# cpu.net
KiCad netlist of a schematic drawn in Altium Designer
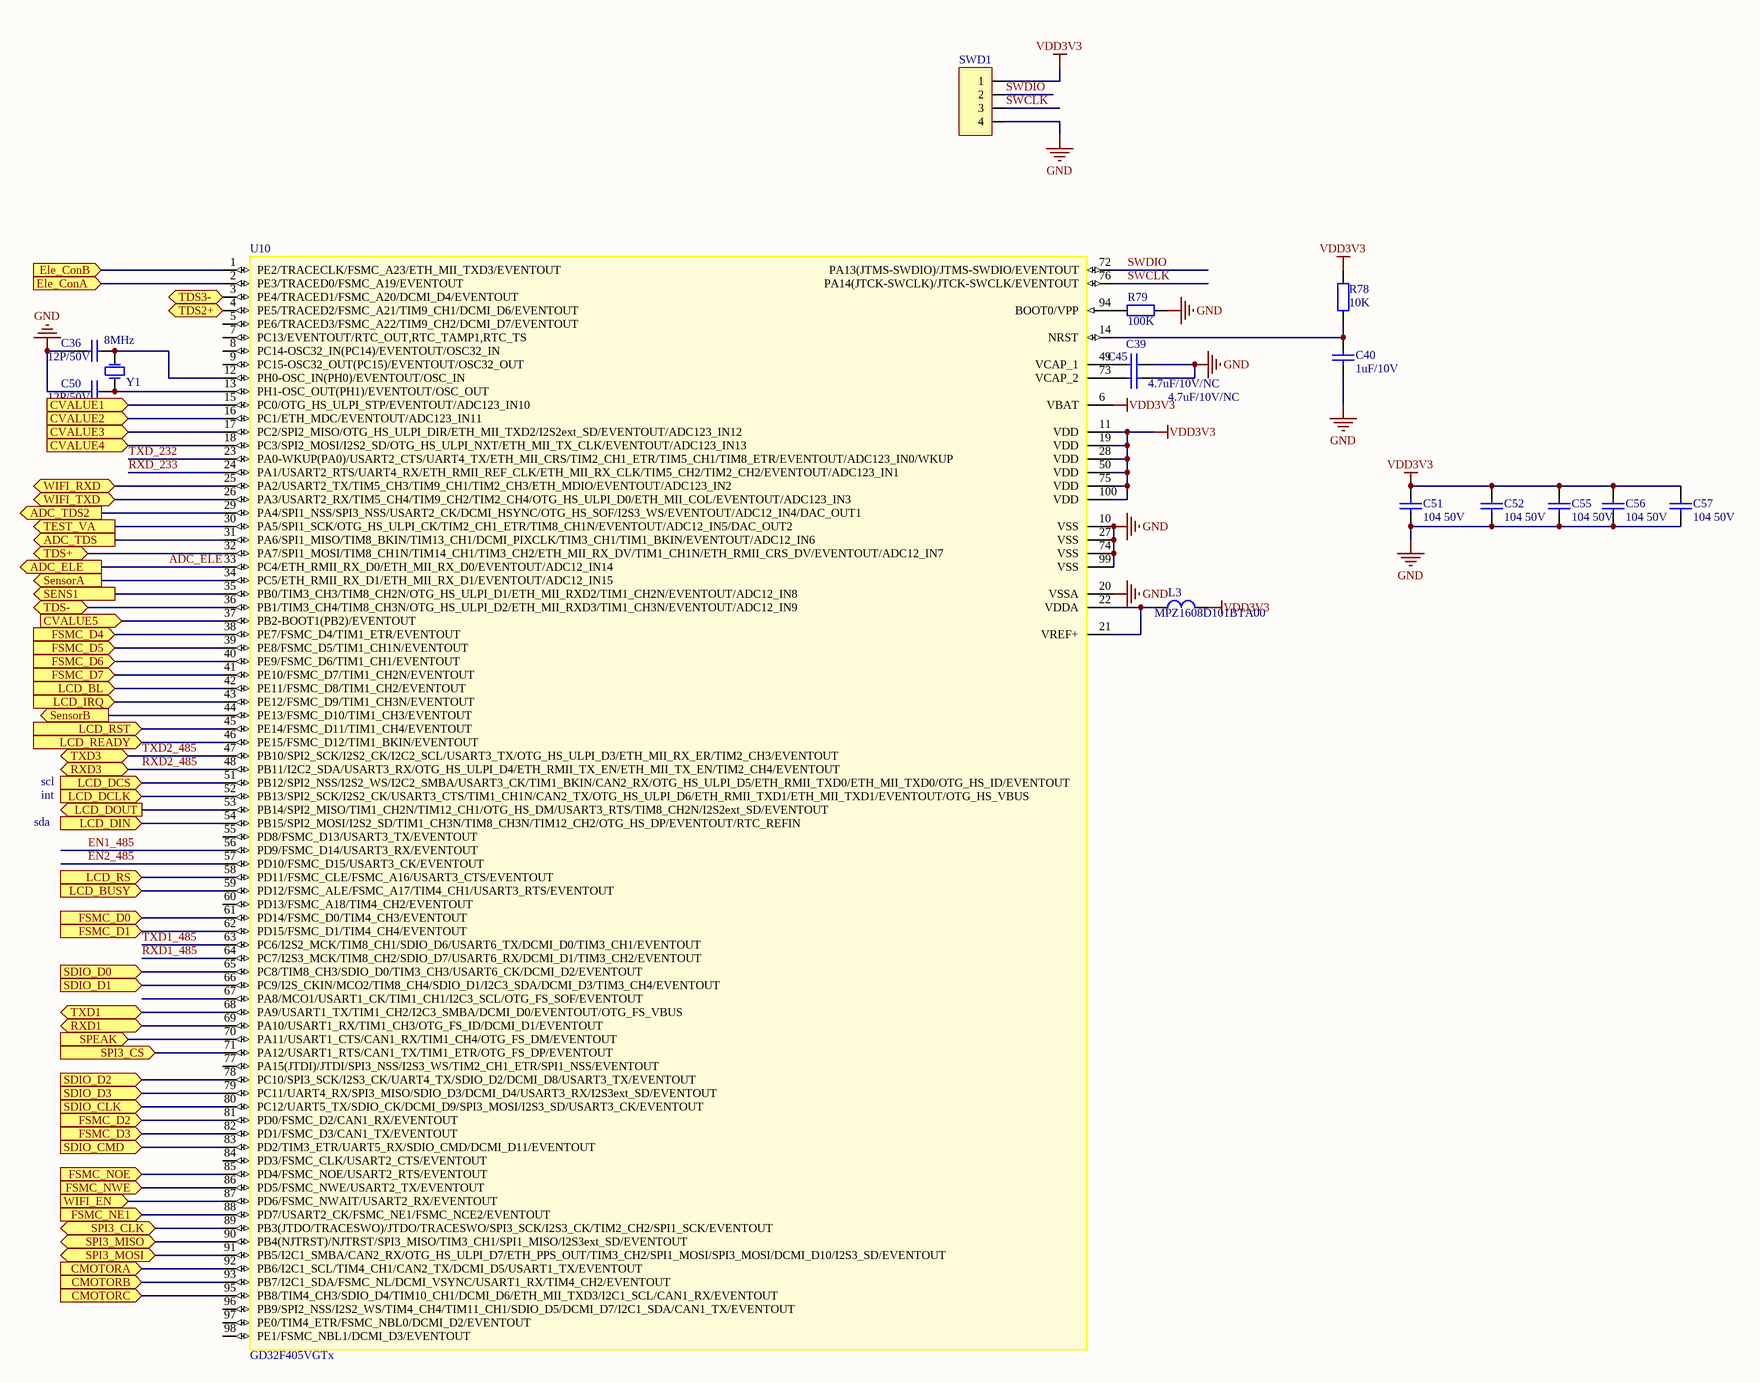
[diagram p0: cpu.SchDoc]

(export (version "E")
  (design (tool "Eeschema 10.0.6"))
  (components
    (comp (ref "C36")
      (value "12P/50V")
      (footprint "SMD-0603C")
      (description "贴片电容 5%")
      (libsource (lib "XiaoyI") (part "CAP4"))
    )
    (comp (ref "C39")
      (value "4.7uF/10V/NC")
      (footprint "SMD-0603C")
      (description "贴片电容 20%")
      (libsource (lib "XiaoyI") (part "CAP4"))
    )
    (comp (ref "C40")
      (value "1uF/10V")
      (footprint "SMD-0603C")
      (description "贴片电容 20%")
      (libsource (lib "XiaoyI") (part "CAP4"))
    )
    (comp (ref "C45")
      (value "4.7uF/10V/NC")
      (footprint "SMD-0603C")
      (description "贴片电容 20%")
      (libsource (lib "XiaoyI") (part "CAP4"))
    )
    (comp (ref "C50")
      (value "12P/50V")
      (footprint "SMD-0603C")
      (description "贴片电容 5%")
      (libsource (lib "XiaoyI") (part "CAP4"))
    )
    (comp (ref "C51")
      (value "104 50V")
      (footprint "SMD-0603C")
      (description "贴片电容 20%")
      (libsource (lib "XiaoyI") (part "CAP4"))
    )
    (comp (ref "C52")
      (value "104 50V")
      (footprint "SMD-0603C")
      (description "贴片电容 20%")
      (libsource (lib "XiaoyI") (part "CAP4"))
    )
    (comp (ref "C55")
      (value "104 50V")
      (footprint "SMD-0603C")
      (description "贴片电容 20%")
      (libsource (lib "XiaoyI") (part "CAP4"))
    )
    (comp (ref "C56")
      (value "104 50V")
      (footprint "SMD-0603C")
      (description "贴片电容 20%")
      (libsource (lib "XiaoyI") (part "CAP4"))
    )
    (comp (ref "C57")
      (value "104 50V")
      (footprint "SMD-0603C")
      (description "贴片电容 20%")
      (libsource (lib "XiaoyI") (part "CAP4"))
    )
    (comp (ref "L3")
      (value "MPZ1608D101BTA00")
      (footprint "SMD-0603")
      (description "磁珠电感 100R 100MHz")
      (libsource (lib "XiaoyI") (part "CIZHU1"))
    )
    (comp (ref "R78")
      (value "10K")
      (footprint "SMD-0603")
      (description "贴片电阻 5%")
      (libsource (lib "XiaoyI") (part "RES2"))
    )
    (comp (ref "R79")
      (value "100K")
      (footprint "SMD-0603")
      (description "贴片电阻 5%")
      (libsource (lib "") (part "RES2_1"))
    )
    (comp (ref "SWD1")
      (value "SIP-4 (NC)")
      (footprint "SIP-4")
      (description "ISP 下载")
      (libsource (lib "XiaoyI") (part "SIP-4"))
    )
    (comp (ref "U10")
      (value "GD32F405VGTx")
      (footprint "STM-LQFP100_N")
      (fields (field (name "MANUFACTURER") "STMicroelectronics") (field (name "PARTNUMBER") "STM32F405VGT6"))
      (libsource (lib "STM32F4") (part "STM32F405VGTx"))
    )
    (comp (ref "Y1")
      (value "8MHz")
      (footprint "XTAL-3225-2")
      (description "3225 贴片晶振")
      (libsource (lib "XiaoyI") (part "XTAL"))
    )
  )
  (nets
    (net (code "1") (name "/ADC_ELE") (class "Default")
      (node (ref "U10") (pin "33") (pinfunction "PC4/ETH_RMII_RX_D0/ETH_MII_RX_D0/EVENTOUT/ADC12_IN14_33") (pintype "bidirectional"))
    )
    (net (code "2") (name "/ADC_TDS") (class "Default")
      (node (ref "U10") (pin "31") (pinfunction "PA6/SPI1_MISO/TIM8_BKIN/TIM13_CH1/DCMI_PIXCLK/TIM3_CH1/TIM1_BKIN/EVENTOUT/ADC12_IN6_31") (pintype "bidirectional"))
    )
    (net (code "3") (name "/ADC_TDS2") (class "Default")
      (node (ref "U10") (pin "29") (pinfunction "PA4/SPI1_NSS/SPI3_NSS/USART2_CK/DCMI_HSYNC/OTG_HS_SOF/I2S3_WS/EVENTOUT/ADC12_IN4/DAC_OUT1_29") (pintype "bidirectional"))
    )
    (net (code "4") (name "/CMOTORA") (class "Default")
      (node (ref "U10") (pin "92") (pinfunction "PB6/I2C1_SCL/TIM4_CH1/CAN2_TX/DCMI_D5/USART1_TX/EVENTOUT_92") (pintype "bidirectional"))
    )
    (net (code "5") (name "/CMOTORB") (class "Default")
      (node (ref "U10") (pin "93") (pinfunction "PB7/I2C1_SDA/FSMC_NL/DCMI_VSYNC/USART1_RX/TIM4_CH2/EVENTOUT_93") (pintype "bidirectional"))
    )
    (net (code "6") (name "/CMOTORC") (class "Default")
      (node (ref "U10") (pin "95") (pinfunction "PB8/TIM4_CH3/SDIO_D4/TIM10_CH1/DCMI_D6/ETH_MII_TXD3/I2C1_SCL/CAN1_RX/EVENTOUT_95") (pintype "bidirectional"))
    )
    (net (code "7") (name "/CVALUE1") (class "Default")
      (node (ref "U10") (pin "15") (pinfunction "PC0/OTG_HS_ULPI_STP/EVENTOUT/ADC123_IN10_15") (pintype "bidirectional"))
    )
    (net (code "8") (name "/CVALUE2") (class "Default")
      (node (ref "U10") (pin "16") (pinfunction "PC1/ETH_MDC/EVENTOUT/ADC123_IN11_16") (pintype "bidirectional"))
    )
    (net (code "9") (name "/CVALUE3") (class "Default")
      (node (ref "U10") (pin "17") (pinfunction "PC2/SPI2_MISO/OTG_HS_ULPI_DIR/ETH_MII_TXD2/I2S2ext_SD/EVENTOUT/ADC123_IN12_17") (pintype "bidirectional"))
    )
    (net (code "10") (name "/CVALUE4") (class "Default")
      (node (ref "U10") (pin "18") (pinfunction "PC3/SPI2_MOSI/I2S2_SD/OTG_HS_ULPI_NXT/ETH_MII_TX_CLK/EVENTOUT/ADC123_IN13_18") (pintype "bidirectional"))
    )
    (net (code "11") (name "/CVALUE5") (class "Default")
      (node (ref "U10") (pin "37") (pinfunction "PB2-BOOT1(PB2)/EVENTOUT_37") (pintype "bidirectional"))
    )
    (net (code "12") (name "/EN1_485") (class "Default")
      (node (ref "U10") (pin "56") (pinfunction "PD9/FSMC_D14/USART3_RX/EVENTOUT_56") (pintype "bidirectional"))
    )
    (net (code "13") (name "/EN2_485") (class "Default")
      (node (ref "U10") (pin "57") (pinfunction "PD10/FSMC_D15/USART3_CK/EVENTOUT_57") (pintype "bidirectional"))
    )
    (net (code "14") (name "/Ele_ConA") (class "Default")
      (node (ref "U10") (pin "2") (pinfunction "PE3/TRACED0/FSMC_A19/EVENTOUT_2") (pintype "bidirectional"))
    )
    (net (code "15") (name "/Ele_ConB") (class "Default")
      (node (ref "U10") (pin "1") (pinfunction "PE2/TRACECLK/FSMC_A23/ETH_MII_TXD3/EVENTOUT_1") (pintype "bidirectional"))
    )
    (net (code "16") (name "/FSMC_D0") (class "Default")
      (node (ref "U10") (pin "61") (pinfunction "PD14/FSMC_D0/TIM4_CH3/EVENTOUT_61") (pintype "bidirectional"))
    )
    (net (code "17") (name "/FSMC_D1") (class "Default")
      (node (ref "U10") (pin "62") (pinfunction "PD15/FSMC_D1/TIM4_CH4/EVENTOUT_62") (pintype "bidirectional"))
    )
    (net (code "18") (name "/FSMC_D2") (class "Default")
      (node (ref "U10") (pin "81") (pinfunction "PD0/FSMC_D2/CAN1_RX/EVENTOUT_81") (pintype "bidirectional"))
    )
    (net (code "19") (name "/FSMC_D3") (class "Default")
      (node (ref "U10") (pin "82") (pinfunction "PD1/FSMC_D3/CAN1_TX/EVENTOUT_82") (pintype "bidirectional"))
    )
    (net (code "20") (name "/FSMC_D4") (class "Default")
      (node (ref "U10") (pin "38") (pinfunction "PE7/FSMC_D4/TIM1_ETR/EVENTOUT_38") (pintype "bidirectional"))
    )
    (net (code "21") (name "/FSMC_D5") (class "Default")
      (node (ref "U10") (pin "39") (pinfunction "PE8/FSMC_D5/TIM1_CH1N/EVENTOUT_39") (pintype "bidirectional"))
    )
    (net (code "22") (name "/FSMC_D6") (class "Default")
      (node (ref "U10") (pin "40") (pinfunction "PE9/FSMC_D6/TIM1_CH1/EVENTOUT_40") (pintype "bidirectional"))
    )
    (net (code "23") (name "/FSMC_D7") (class "Default")
      (node (ref "U10") (pin "41") (pinfunction "PE10/FSMC_D7/TIM1_CH2N/EVENTOUT_41") (pintype "bidirectional"))
    )
    (net (code "24") (name "/FSMC_NE1") (class "Default")
      (node (ref "U10") (pin "88") (pinfunction "PD7/USART2_CK/FSMC_NE1/FSMC_NCE2/EVENTOUT_88") (pintype "bidirectional"))
    )
    (net (code "25") (name "/FSMC_NOE") (class "Default")
      (node (ref "U10") (pin "85") (pinfunction "PD4/FSMC_NOE/USART2_RTS/EVENTOUT_85") (pintype "bidirectional"))
    )
    (net (code "26") (name "/FSMC_NWE") (class "Default")
      (node (ref "U10") (pin "86") (pinfunction "PD5/FSMC_NWE/USART2_TX/EVENTOUT_86") (pintype "bidirectional"))
    )
    (net (code "27") (name "/LCD_BL") (class "Default")
      (node (ref "U10") (pin "42") (pinfunction "PE11/FSMC_D8/TIM1_CH2/EVENTOUT_42") (pintype "bidirectional"))
    )
    (net (code "28") (name "/LCD_BUSY") (class "Default")
      (node (ref "U10") (pin "59") (pinfunction "PD12/FSMC_ALE/FSMC_A17/TIM4_CH1/USART3_RTS/EVENTOUT_59") (pintype "bidirectional"))
    )
    (net (code "29") (name "/LCD_DCLK") (class "Default")
      (node (ref "U10") (pin "52") (pinfunction "PB13/SPI2_SCK/I2S2_CK/USART3_CTS/TIM1_CH1N/CAN2_TX/OTG_HS_ULPI_D6/ETH_RMII_TXD1/ETH_MII_TXD1/EVENTOUT/OTG_HS_VBUS_52") (pintype "bidirectional"))
    )
    (net (code "30") (name "/LCD_DCS") (class "Default")
      (node (ref "U10") (pin "51") (pinfunction "PB12/SPI2_NSS/I2S2_WS/I2C2_SMBA/USART3_CK/TIM1_BKIN/CAN2_RX/OTG_HS_ULPI_D5/ETH_RMII_TXD0/ETH_MII_TXD0/OTG_HS_ID/EVENTOUT_51") (pintype "bidirectional"))
    )
    (net (code "31") (name "/LCD_DIN") (class "Default")
      (node (ref "U10") (pin "54") (pinfunction "PB15/SPI2_MOSI/I2S2_SD/TIM1_CH3N/TIM8_CH3N/TIM12_CH2/OTG_HS_DP/EVENTOUT/RTC_REFIN_54") (pintype "bidirectional"))
    )
    (net (code "32") (name "/LCD_DOUT") (class "Default")
      (node (ref "U10") (pin "53") (pinfunction "PB14/SPI2_MISO/TIM1_CH2N/TIM12_CH1/OTG_HS_DM/USART3_RTS/TIM8_CH2N/I2S2ext_SD/EVENTOUT_53") (pintype "bidirectional"))
    )
    (net (code "33") (name "/LCD_IRQ") (class "Default")
      (node (ref "U10") (pin "43") (pinfunction "PE12/FSMC_D9/TIM1_CH3N/EVENTOUT_43") (pintype "bidirectional"))
    )
    (net (code "34") (name "/LCD_READY") (class "Default")
      (node (ref "U10") (pin "46") (pinfunction "PE15/FSMC_D12/TIM1_BKIN/EVENTOUT_46") (pintype "bidirectional"))
    )
    (net (code "35") (name "/LCD_RS") (class "Default")
      (node (ref "U10") (pin "58") (pinfunction "PD11/FSMC_CLE/FSMC_A16/USART3_CTS/EVENTOUT_58") (pintype "bidirectional"))
    )
    (net (code "36") (name "/LCD_RST") (class "Default")
      (node (ref "U10") (pin "45") (pinfunction "PE14/FSMC_D11/TIM1_CH4/EVENTOUT_45") (pintype "bidirectional"))
    )
    (net (code "37") (name "/RXD1") (class "Default")
      (node (ref "U10") (pin "69") (pinfunction "PA10/USART1_RX/TIM1_CH3/OTG_FS_ID/DCMI_D1/EVENTOUT_69") (pintype "bidirectional"))
    )
    (net (code "38") (name "/RXD1_485") (class "Default")
      (node (ref "U10") (pin "64") (pinfunction "PC7/I2S3_MCK/TIM8_CH2/SDIO_D7/USART6_RX/DCMI_D1/TIM3_CH2/EVENTOUT_64") (pintype "bidirectional"))
    )
    (net (code "39") (name "/RXD2_485") (class "Default")
      (node (ref "U10") (pin "48") (pinfunction "PB11/I2C2_SDA/USART3_RX/OTG_HS_ULPI_D4/ETH_RMII_TX_EN/ETH_MII_TX_EN/TIM2_CH4/EVENTOUT_48") (pintype "bidirectional"))
    )
    (net (code "40") (name "/RXD_233") (class "Default")
      (node (ref "U10") (pin "24") (pinfunction "PA1/USART2_RTS/UART4_RX/ETH_RMII_REF_CLK/ETH_MII_RX_CLK/TIM5_CH2/TIM2_CH2/EVENTOUT/ADC123_IN1_24") (pintype "bidirectional"))
    )
    (net (code "41") (name "/SDIO_CLK") (class "Default")
      (node (ref "U10") (pin "80") (pinfunction "PC12/UART5_TX/SDIO_CK/DCMI_D9/SPI3_MOSI/I2S3_SD/USART3_CK/EVENTOUT_80") (pintype "bidirectional"))
    )
    (net (code "42") (name "/SDIO_CMD") (class "Default")
      (node (ref "U10") (pin "83") (pinfunction "PD2/TIM3_ETR/UART5_RX/SDIO_CMD/DCMI_D11/EVENTOUT_83") (pintype "bidirectional"))
    )
    (net (code "43") (name "/SDIO_D0") (class "Default")
      (node (ref "U10") (pin "65") (pinfunction "PC8/TIM8_CH3/SDIO_D0/TIM3_CH3/USART6_CK/DCMI_D2/EVENTOUT_65") (pintype "bidirectional"))
    )
    (net (code "44") (name "/SDIO_D1") (class "Default")
      (node (ref "U10") (pin "66") (pinfunction "PC9/I2S_CKIN/MCO2/TIM8_CH4/SDIO_D1/I2C3_SDA/DCMI_D3/TIM3_CH4/EVENTOUT_66") (pintype "bidirectional"))
    )
    (net (code "45") (name "/SDIO_D2") (class "Default")
      (node (ref "U10") (pin "78") (pinfunction "PC10/SPI3_SCK/I2S3_CK/UART4_TX/SDIO_D2/DCMI_D8/USART3_TX/EVENTOUT_78") (pintype "bidirectional"))
    )
    (net (code "46") (name "/SDIO_D3") (class "Default")
      (node (ref "U10") (pin "79") (pinfunction "PC11/UART4_RX/SPI3_MISO/SDIO_D3/DCMI_D4/USART3_RX/I2S3ext_SD/EVENTOUT_79") (pintype "bidirectional"))
    )
    (net (code "47") (name "/SENS1") (class "Default")
      (node (ref "U10") (pin "35") (pinfunction "PB0/TIM3_CH3/TIM8_CH2N/OTG_HS_ULPI_D1/ETH_MII_RXD2/TIM1_CH2N/EVENTOUT/ADC12_IN8_35") (pintype "bidirectional"))
    )
    (net (code "48") (name "/SPEAK") (class "Default")
      (node (ref "U10") (pin "70") (pinfunction "PA11/USART1_CTS/CAN1_RX/TIM1_CH4/OTG_FS_DM/EVENTOUT_70") (pintype "bidirectional"))
    )
    (net (code "49") (name "/SPI3_CLK") (class "Default")
      (node (ref "U10") (pin "89") (pinfunction "PB3(JTDO/TRACESWO)/JTDO/TRACESWO/SPI3_SCK/I2S3_CK/TIM2_CH2/SPI1_SCK/EVENTOUT_89") (pintype "bidirectional"))
    )
    (net (code "50") (name "/SPI3_CS") (class "Default")
      (node (ref "U10") (pin "71") (pinfunction "PA12/USART1_RTS/CAN1_TX/TIM1_ETR/OTG_FS_DP/EVENTOUT_71") (pintype "bidirectional"))
    )
    (net (code "51") (name "/SPI3_MISO") (class "Default")
      (node (ref "U10") (pin "90") (pinfunction "PB4(NJTRST)/NJTRST/SPI3_MISO/TIM3_CH1/SPI1_MISO/I2S3ext_SD/EVENTOUT_90") (pintype "bidirectional"))
    )
    (net (code "52") (name "/SPI3_MOSI") (class "Default")
      (node (ref "U10") (pin "91") (pinfunction "PB5/I2C1_SMBA/CAN2_RX/OTG_HS_ULPI_D7/ETH_PPS_OUT/TIM3_CH2/SPI1_MOSI/SPI3_MOSI/DCMI_D10/I2S3_SD/EVENTOUT_91") (pintype "bidirectional"))
    )
    (net (code "53") (name "/SWCLK") (class "Default")
      (node (ref "SWD1") (pin "3") (pinfunction "3_3") (pintype "passive"))
      (node (ref "U10") (pin "76") (pinfunction "PA14(JTCK-SWCLK)/JTCK-SWCLK/EVENTOUT_76") (pintype "bidirectional"))
    )
    (net (code "54") (name "/SWDIO") (class "Default")
      (node (ref "SWD1") (pin "2") (pinfunction "2_2") (pintype "passive"))
      (node (ref "U10") (pin "72") (pinfunction "PA13(JTMS-SWDIO)/JTMS-SWDIO/EVENTOUT_72") (pintype "bidirectional"))
    )
    (net (code "55") (name "/SensorA") (class "Default")
      (node (ref "U10") (pin "34") (pinfunction "PC5/ETH_RMII_RX_D1/ETH_MII_RX_D1/EVENTOUT/ADC12_IN15_34") (pintype "bidirectional"))
    )
    (net (code "56") (name "/SensorB") (class "Default")
      (node (ref "U10") (pin "44") (pinfunction "PE13/FSMC_D10/TIM1_CH3/EVENTOUT_44") (pintype "bidirectional"))
    )
    (net (code "57") (name "/TDS+") (class "Default")
      (node (ref "U10") (pin "32") (pinfunction "PA7/SPI1_MOSI/TIM8_CH1N/TIM14_CH1/TIM3_CH2/ETH_MII_RX_DV/TIM1_CH1N/ETH_RMII_CRS_DV/EVENTOUT/ADC12_IN7_32") (pintype "bidirectional"))
    )
    (net (code "58") (name "/TDS-") (class "Default")
      (node (ref "U10") (pin "36") (pinfunction "PB1/TIM3_CH4/TIM8_CH3N/OTG_HS_ULPI_D2/ETH_MII_RXD3/TIM1_CH3N/EVENTOUT/ADC12_IN9_36") (pintype "bidirectional"))
    )
    (net (code "59") (name "/TDS2+") (class "Default")
      (node (ref "U10") (pin "4") (pinfunction "PE5/TRACED2/FSMC_A21/TIM9_CH1/DCMI_D6/EVENTOUT_4") (pintype "bidirectional"))
    )
    (net (code "60") (name "/TDS3-") (class "Default")
      (node (ref "U10") (pin "3") (pinfunction "PE4/TRACED1/FSMC_A20/DCMI_D4/EVENTOUT_3") (pintype "bidirectional"))
    )
    (net (code "61") (name "/TEST_VA") (class "Default")
      (node (ref "U10") (pin "30") (pinfunction "PA5/SPI1_SCK/OTG_HS_ULPI_CK/TIM2_CH1_ETR/TIM8_CH1N/EVENTOUT/ADC12_IN5/DAC_OUT2_30") (pintype "bidirectional"))
    )
    (net (code "62") (name "/TXD1") (class "Default")
      (node (ref "U10") (pin "68") (pinfunction "PA9/USART1_TX/TIM1_CH2/I2C3_SMBA/DCMI_D0/EVENTOUT/OTG_FS_VBUS_68") (pintype "bidirectional"))
    )
    (net (code "63") (name "/TXD1_485") (class "Default")
      (node (ref "U10") (pin "63") (pinfunction "PC6/I2S2_MCK/TIM8_CH1/SDIO_D6/USART6_TX/DCMI_D0/TIM3_CH1/EVENTOUT_63") (pintype "bidirectional"))
    )
    (net (code "64") (name "/TXD2_485") (class "Default")
      (node (ref "U10") (pin "47") (pinfunction "PB10/SPI2_SCK/I2S2_CK/I2C2_SCL/USART3_TX/OTG_HS_ULPI_D3/ETH_MII_RX_ER/TIM2_CH3/EVENTOUT_47") (pintype "bidirectional"))
    )
    (net (code "65") (name "/TXD_232") (class "Default")
      (node (ref "U10") (pin "23") (pinfunction "PA0-WKUP(PA0)/USART2_CTS/UART4_TX/ETH_MII_CRS/TIM2_CH1_ETR/TIM5_CH1/TIM8_ETR/EVENTOUT/ADC123_IN0/WKUP_23") (pintype "bidirectional"))
    )
    (net (code "66") (name "/WIFI_EN") (class "Default")
      (node (ref "U10") (pin "87") (pinfunction "PD6/FSMC_NWAIT/USART2_RX/EVENTOUT_87") (pintype "bidirectional"))
    )
    (net (code "67") (name "/WIFI_RXD") (class "Default")
      (node (ref "U10") (pin "25") (pinfunction "PA2/USART2_TX/TIM5_CH3/TIM9_CH1/TIM2_CH3/ETH_MDIO/EVENTOUT/ADC123_IN2_25") (pintype "bidirectional"))
    )
    (net (code "68") (name "/WIFI_TXD") (class "Default")
      (node (ref "U10") (pin "26") (pinfunction "PA3/USART2_RX/TIM5_CH4/TIM9_CH2/TIM2_CH4/OTG_HS_ULPI_D0/ETH_MII_COL/EVENTOUT/ADC123_IN3_26") (pintype "bidirectional"))
    )
    (net (code "69") (name "GND") (class "Default")
      (node (ref "C36") (pin "2") (pinfunction "2_2") (pintype "passive"))
      (node (ref "C39") (pin "1") (pinfunction "1_1") (pintype "passive"))
      (node (ref "C40") (pin "1") (pinfunction "1_1") (pintype "passive"))
      (node (ref "C45") (pin "1") (pinfunction "1_1") (pintype "passive"))
      (node (ref "C50") (pin "2") (pinfunction "2_2") (pintype "passive"))
      (node (ref "C51") (pin "1") (pinfunction "1_1") (pintype "passive"))
      (node (ref "C52") (pin "1") (pinfunction "1_1") (pintype "passive"))
      (node (ref "C55") (pin "1") (pinfunction "1_1") (pintype "passive"))
      (node (ref "C56") (pin "1") (pinfunction "1_1") (pintype "passive"))
      (node (ref "C57") (pin "1") (pinfunction "1_1") (pintype "passive"))
      (node (ref "R79") (pin "1") (pinfunction "1_1") (pintype "passive"))
      (node (ref "SWD1") (pin "4") (pinfunction "4_4") (pintype "passive"))
      (node (ref "U10") (pin "10") (pinfunction "VSS_10") (pintype "power_in"))
      (node (ref "U10") (pin "20") (pinfunction "VSSA_20") (pintype "power_in"))
      (node (ref "U10") (pin "27") (pinfunction "VSS_27") (pintype "power_in"))
      (node (ref "U10") (pin "74") (pinfunction "VSS_74") (pintype "power_in"))
      (node (ref "U10") (pin "99") (pinfunction "VSS_99") (pintype "power_in"))
    )
    (net (code "70") (name "Net-(U10-BOOT0{slash}VPP)") (class "Default")
      (node (ref "R79") (pin "2") (pinfunction "2_2") (pintype "passive"))
      (node (ref "U10") (pin "94") (pinfunction "BOOT0/VPP_94") (pintype "input"))
    )
    (net (code "71") (name "Net-(U10-NRST)") (class "Default")
      (node (ref "C40") (pin "2") (pinfunction "2_2") (pintype "passive"))
      (node (ref "R78") (pin "1") (pinfunction "1_1") (pintype "passive"))
      (node (ref "U10") (pin "14") (pinfunction "NRST_14") (pintype "bidirectional"))
    )
    (net (code "72") (name "Net-(U10-PH0-OSC_IN(PH0){slash}EVENTOUT{slash}OSC_IN)") (class "Default")
      (node (ref "C36") (pin "1") (pinfunction "1_1") (pintype "passive"))
      (node (ref "U10") (pin "12") (pinfunction "PH0-OSC_IN(PH0)/EVENTOUT/OSC_IN_12") (pintype "bidirectional"))
      (node (ref "Y1") (pin "2") (pinfunction "OSC2_2") (pintype "passive"))
    )
    (net (code "73") (name "Net-(U10-PH1-OSC_OUT(PH1){slash}EVENTOUT{slash}OSC_OUT)") (class "Default")
      (node (ref "C50") (pin "1") (pinfunction "1_1") (pintype "passive"))
      (node (ref "U10") (pin "13") (pinfunction "PH1-OSC_OUT(PH1)/EVENTOUT/OSC_OUT_13") (pintype "bidirectional"))
      (node (ref "Y1") (pin "1") (pinfunction "OSC1_1") (pintype "passive"))
    )
    (net (code "74") (name "Net-(U10-VCAP_1)") (class "Default")
      (node (ref "C39") (pin "2") (pinfunction "2_2") (pintype "passive"))
      (node (ref "U10") (pin "49") (pinfunction "VCAP_1_49") (pintype "power_in"))
    )
    (net (code "75") (name "Net-(U10-VCAP_2)") (class "Default")
      (node (ref "C45") (pin "2") (pinfunction "2_2") (pintype "passive"))
      (node (ref "U10") (pin "73") (pinfunction "VCAP_2_73") (pintype "power_in"))
    )
    (net (code "76") (name "Net-(U10-VDDA)") (class "Default")
      (node (ref "L3") (pin "2") (pinfunction "2_2") (pintype "passive"))
      (node (ref "U10") (pin "21") (pinfunction "VREF+_21") (pintype "power_in"))
      (node (ref "U10") (pin "22") (pinfunction "VDDA_22") (pintype "power_in"))
    )
    (net (code "77") (name "VDD3V3") (class "Default")
      (node (ref "C51") (pin "2") (pinfunction "2_2") (pintype "passive"))
      (node (ref "C52") (pin "2") (pinfunction "2_2") (pintype "passive"))
      (node (ref "C55") (pin "2") (pinfunction "2_2") (pintype "passive"))
      (node (ref "C56") (pin "2") (pinfunction "2_2") (pintype "passive"))
      (node (ref "C57") (pin "2") (pinfunction "2_2") (pintype "passive"))
      (node (ref "L3") (pin "1") (pinfunction "1_1") (pintype "passive"))
      (node (ref "R78") (pin "2") (pinfunction "2_2") (pintype "passive"))
      (node (ref "SWD1") (pin "1") (pinfunction "1_1") (pintype "passive"))
      (node (ref "U10") (pin "100") (pinfunction "VDD_100") (pintype "power_in"))
      (node (ref "U10") (pin "11") (pinfunction "VDD_11") (pintype "power_in"))
      (node (ref "U10") (pin "19") (pinfunction "VDD_19") (pintype "power_in"))
      (node (ref "U10") (pin "28") (pinfunction "VDD_28") (pintype "power_in"))
      (node (ref "U10") (pin "50") (pinfunction "VDD_50") (pintype "power_in"))
      (node (ref "U10") (pin "6") (pinfunction "VBAT_6") (pintype "power_in"))
      (node (ref "U10") (pin "75") (pinfunction "VDD_75") (pintype "power_in"))
    )
    (net (code "78") (name "unconnected-(U10-PA8{slash}MCO1{slash}USART1_CK{slash}TIM1_CH1{slash}I2C3_SCL{slash}OTG_FS_SOF{slash}EVENTOUT-Pad67)") (class "Default")
      (node (ref "U10") (pin "67") (pinfunction "PA8/MCO1/USART1_CK/TIM1_CH1/I2C3_SCL/OTG_FS_SOF/EVENTOUT_67") (pintype "bidirectional"))
    )
    (net (code "79") (name "unconnected-(U10-PA15(JTDI){slash}JTDI{slash}SPI3_NSS{slash}I2S3_WS{slash}TIM2_CH1_ETR{slash}SPI1_NSS{slash}EVENTOUT-Pad77)") (class "Default")
      (node (ref "U10") (pin "77") (pinfunction "PA15(JTDI)/JTDI/SPI3_NSS/I2S3_WS/TIM2_CH1_ETR/SPI1_NSS/EVENTOUT_77") (pintype "bidirectional"))
    )
    (net (code "80") (name "unconnected-(U10-PB9{slash}SPI2_NSS{slash}I2S2_WS{slash}TIM4_CH4{slash}TIM11_CH1{slash}SDIO_D5{slash}DCMI_D7{slash}I2C1_SDA{slash}CAN1_TX{slash}EVENTOUT-Pad96)") (class "Default")
      (node (ref "U10") (pin "96") (pinfunction "PB9/SPI2_NSS/I2S2_WS/TIM4_CH4/TIM11_CH1/SDIO_D5/DCMI_D7/I2C1_SDA/CAN1_TX/EVENTOUT_96") (pintype "bidirectional"))
    )
    (net (code "81") (name "unconnected-(U10-PC13{slash}EVENTOUT{slash}RTC_OUT,RTC_TAMP1,RTC_TS-Pad7)") (class "Default")
      (node (ref "U10") (pin "7") (pinfunction "PC13/EVENTOUT/RTC_OUT,RTC_TAMP1,RTC_TS_7") (pintype "bidirectional"))
    )
    (net (code "82") (name "unconnected-(U10-PC14-OSC32_IN(PC14){slash}EVENTOUT{slash}OSC32_IN-Pad8)") (class "Default")
      (node (ref "U10") (pin "8") (pinfunction "PC14-OSC32_IN(PC14)/EVENTOUT/OSC32_IN_8") (pintype "bidirectional"))
    )
    (net (code "83") (name "unconnected-(U10-PC15-OSC32_OUT(PC15){slash}EVENTOUT{slash}OSC32_OUT-Pad9)") (class "Default")
      (node (ref "U10") (pin "9") (pinfunction "PC15-OSC32_OUT(PC15)/EVENTOUT/OSC32_OUT_9") (pintype "bidirectional"))
    )
    (net (code "84") (name "unconnected-(U10-PD3{slash}FSMC_CLK{slash}USART2_CTS{slash}EVENTOUT-Pad84)") (class "Default")
      (node (ref "U10") (pin "84") (pinfunction "PD3/FSMC_CLK/USART2_CTS/EVENTOUT_84") (pintype "bidirectional"))
    )
    (net (code "85") (name "unconnected-(U10-PD8{slash}FSMC_D13{slash}USART3_TX{slash}EVENTOUT-Pad55)") (class "Default")
      (node (ref "U10") (pin "55") (pinfunction "PD8/FSMC_D13/USART3_TX/EVENTOUT_55") (pintype "bidirectional"))
    )
    (net (code "86") (name "unconnected-(U10-PD13{slash}FSMC_A18{slash}TIM4_CH2{slash}EVENTOUT-Pad60)") (class "Default")
      (node (ref "U10") (pin "60") (pinfunction "PD13/FSMC_A18/TIM4_CH2/EVENTOUT_60") (pintype "bidirectional"))
    )
    (net (code "87") (name "unconnected-(U10-PE0{slash}TIM4_ETR{slash}FSMC_NBL0{slash}DCMI_D2{slash}EVENTOUT-Pad97)") (class "Default")
      (node (ref "U10") (pin "97") (pinfunction "PE0/TIM4_ETR/FSMC_NBL0/DCMI_D2/EVENTOUT_97") (pintype "bidirectional"))
    )
    (net (code "88") (name "unconnected-(U10-PE1{slash}FSMC_NBL1{slash}DCMI_D3{slash}EVENTOUT-Pad98)") (class "Default")
      (node (ref "U10") (pin "98") (pinfunction "PE1/FSMC_NBL1/DCMI_D3/EVENTOUT_98") (pintype "bidirectional"))
    )
    (net (code "89") (name "unconnected-(U10-PE6{slash}TRACED3{slash}FSMC_A22{slash}TIM9_CH2{slash}DCMI_D7{slash}EVENTOUT-Pad5)") (class "Default")
      (node (ref "U10") (pin "5") (pinfunction "PE6/TRACED3/FSMC_A22/TIM9_CH2/DCMI_D7/EVENTOUT_5") (pintype "bidirectional"))
    )
  )
)
